# eth_part.net
KiCad netlist of a schematic drawn in Altium Designer
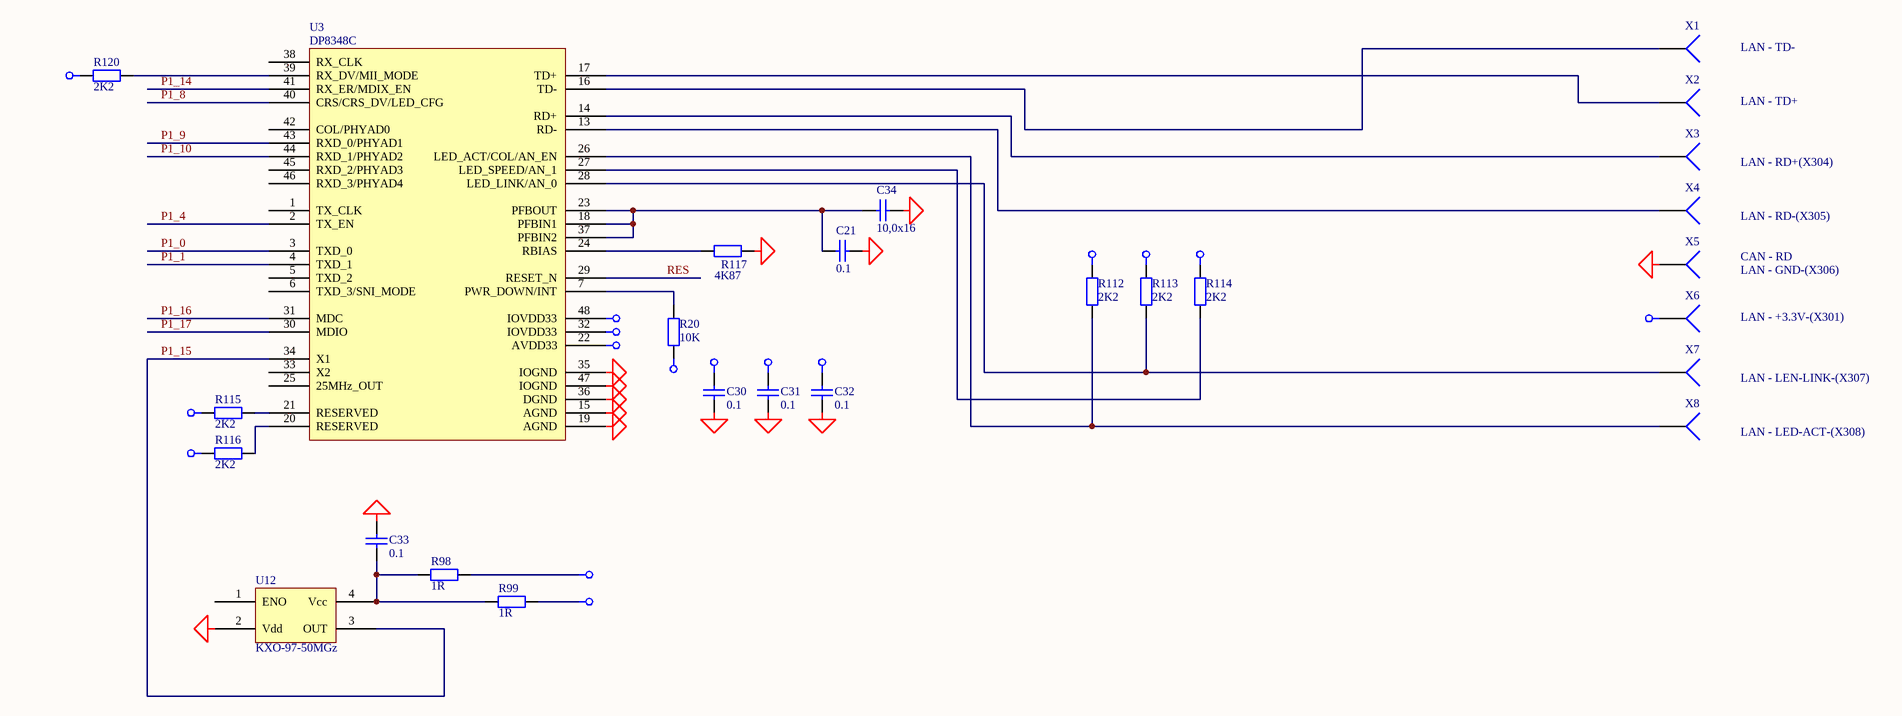
[diagram p0: eth_part.SchDoc]

(export (version "E")
  (design (tool "Eeschema 10.0.6"))
  (components
    (comp (ref "C21")
      (value "0.1")
      (footprint "C3216-1206")
      (description "Capacitor (Semiconductor SIM Model)")
      (fields (field (name "MANUFACTURER") "Generic Components") (field (name "PUBLISHER") "Altium Limited"))
      (libsource (lib "Miscellaneous Devices") (part "Cap Semi"))
    )
    (comp (ref "C30")
      (value "0.1")
      (footprint "_1206")
      (description "Capacitor (Semiconductor SIM Model)")
      (fields (field (name "MANUFACTURER") "Generic Components") (field (name "PUBLISHER") "Altium Limited"))
      (libsource (lib "Miscellaneous Devices") (part "Cap Semi"))
    )
    (comp (ref "C31")
      (value "0.1")
      (footprint "_1206")
      (description "Capacitor (Semiconductor SIM Model)")
      (fields (field (name "MANUFACTURER") "Generic Components") (field (name "PUBLISHER") "Altium Limited"))
      (libsource (lib "Miscellaneous Devices") (part "Cap Semi"))
    )
    (comp (ref "C32")
      (value "0.1")
      (footprint "_1206")
      (description "Capacitor (Semiconductor SIM Model)")
      (fields (field (name "MANUFACTURER") "Generic Components") (field (name "PUBLISHER") "Altium Limited"))
      (libsource (lib "Miscellaneous Devices") (part "Cap Semi"))
    )
    (comp (ref "C33")
      (value "0.1")
      (footprint "_1206")
      (description "Capacitor (Semiconductor SIM Model)")
      (fields (field (name "MANUFACTURER") "Generic Components") (field (name "PUBLISHER") "Altium Limited"))
      (libsource (lib "Miscellaneous Devices") (part "Cap Semi"))
    )
    (comp (ref "C34")
      (value "10,0x16")
      (footprint "C3216-1206")
      (description "Capacitor (Semiconductor SIM Model)")
      (fields (field (name "MANUFACTURER") "Generic Components") (field (name "PUBLISHER") "Altium Limited"))
      (libsource (lib "Miscellaneous Devices") (part "Cap Semi"))
    )
    (comp (ref "R20")
      (value "10K")
      (footprint "_1206")
      (description "Resistor")
      (fields (field (name "MANUFACTURER") "Generic Components") (field (name "PUBLISHER") "Altium Limited"))
      (libsource (lib "") (part "Res2_2"))
    )
    (comp (ref "R98")
      (value "1R")
      (footprint "_1206")
      (description "Resistor")
      (fields (field (name "MANUFACTURER") "Generic Components") (field (name "PUBLISHER") "Altium Limited"))
      (libsource (lib "") (part "Res2_1"))
    )
    (comp (ref "R99")
      (value "1R")
      (footprint "_1206")
      (description "Resistor")
      (fields (field (name "MANUFACTURER") "Generic Components") (field (name "PUBLISHER") "Altium Limited"))
      (libsource (lib "") (part "Res2_1"))
    )
    (comp (ref "R112")
      (value "2K2")
      (footprint "_1206")
      (description "Resistor")
      (fields (field (name "MANUFACTURER") "Generic Components") (field (name "PUBLISHER") "Altium Limited"))
      (libsource (lib "Miscellaneous Devices") (part "Res2"))
    )
    (comp (ref "R113")
      (value "2K2")
      (footprint "_1206")
      (description "Resistor")
      (fields (field (name "MANUFACTURER") "Generic Components") (field (name "PUBLISHER") "Altium Limited"))
      (libsource (lib "Miscellaneous Devices") (part "Res2"))
    )
    (comp (ref "R114")
      (value "2K2")
      (footprint "_1206")
      (description "Resistor")
      (fields (field (name "MANUFACTURER") "Generic Components") (field (name "PUBLISHER") "Altium Limited"))
      (libsource (lib "Miscellaneous Devices") (part "Res2"))
    )
    (comp (ref "R115")
      (value "2K2")
      (footprint "_1206")
      (description "Resistor")
      (fields (field (name "MANUFACTURER") "Generic Components") (field (name "PUBLISHER") "Altium Limited"))
      (libsource (lib "") (part "Res2_3"))
    )
    (comp (ref "R116")
      (value "2K2")
      (footprint "_1206")
      (description "Resistor")
      (fields (field (name "MANUFACTURER") "Generic Components") (field (name "PUBLISHER") "Altium Limited"))
      (libsource (lib "") (part "Res2_3"))
    )
    (comp (ref "R117")
      (value "4K87")
      (footprint "_1206")
      (description "Resistor")
      (fields (field (name "MANUFACTURER") "Generic Components") (field (name "PUBLISHER") "Altium Limited"))
      (libsource (lib "") (part "Res2_3"))
    )
    (comp (ref "R120")
      (value "2K2")
      (footprint "_1206")
      (description "Resistor")
      (fields (field (name "MANUFACTURER") "Generic Components") (field (name "PUBLISHER") "Altium Limited"))
      (libsource (lib "") (part "Res2_3"))
    )
    (comp (ref "U3") (value "DP8348C") (footprint "F-QFP7X7-G48/N") (libsource (lib "PAL") (part "DP8348C")))
    (comp (ref "U12") (value "KXO-97-50MGz") (footprint "KXO-97") (libsource (lib "PAL") (part "KXO-97")))
    (comp (ref "X1")
      (value "~")
      (footprint "PIN1")
      (description "Socket")
      (fields (field (name "MANUFACTURER") "Generic Components") (field (name "PUBLISHER") "Altium Limited"))
      (libsource (lib "Miscellaneous Connectors") (part "Socket"))
    )
    (comp (ref "X2")
      (value "~")
      (footprint "PIN1")
      (description "Socket")
      (fields (field (name "MANUFACTURER") "Generic Components") (field (name "PUBLISHER") "Altium Limited"))
      (libsource (lib "Miscellaneous Connectors") (part "Socket"))
    )
    (comp (ref "X3")
      (value "~")
      (footprint "PIN1")
      (description "Socket")
      (fields (field (name "MANUFACTURER") "Generic Components") (field (name "PUBLISHER") "Altium Limited"))
      (libsource (lib "Miscellaneous Connectors") (part "Socket"))
    )
    (comp (ref "X4")
      (value "~")
      (footprint "PIN1")
      (description "Socket")
      (fields (field (name "MANUFACTURER") "Generic Components") (field (name "PUBLISHER") "Altium Limited"))
      (libsource (lib "Miscellaneous Connectors") (part "Socket"))
    )
    (comp (ref "X5")
      (value "~")
      (footprint "PIN1")
      (description "Socket")
      (fields (field (name "MANUFACTURER") "Generic Components") (field (name "PUBLISHER") "Altium Limited"))
      (libsource (lib "Miscellaneous Connectors") (part "Socket"))
    )
    (comp (ref "X6")
      (value "~")
      (footprint "PIN1")
      (description "Socket")
      (fields (field (name "MANUFACTURER") "Generic Components") (field (name "PUBLISHER") "Altium Limited"))
      (libsource (lib "Miscellaneous Connectors") (part "Socket"))
    )
    (comp (ref "X7")
      (value "~")
      (footprint "PIN1")
      (description "Socket")
      (fields (field (name "MANUFACTURER") "Generic Components") (field (name "PUBLISHER") "Altium Limited"))
      (libsource (lib "Miscellaneous Connectors") (part "Socket"))
    )
    (comp (ref "X8")
      (value "~")
      (footprint "PIN1")
      (description "Socket")
      (fields (field (name "MANUFACTURER") "Generic Components") (field (name "PUBLISHER") "Altium Limited"))
      (libsource (lib "Miscellaneous Connectors") (part "Socket"))
    )
  )
  (nets
    (net (code "1") (name "+3v3") (class "Default")
      (node (ref "C30") (pin "1") (pinfunction "1_1") (pintype "passive"))
      (node (ref "C31") (pin "1") (pinfunction "1_1") (pintype "passive"))
      (node (ref "C32") (pin "1") (pinfunction "1_1") (pintype "passive"))
      (node (ref "R112") (pin "2") (pinfunction "2_2") (pintype "passive"))
      (node (ref "R113") (pin "2") (pinfunction "2_2") (pintype "passive"))
      (node (ref "R114") (pin "2") (pinfunction "2_2") (pintype "passive"))
      (node (ref "R115") (pin "2") (pinfunction "2_2") (pintype "passive"))
      (node (ref "R116") (pin "2") (pinfunction "2_2") (pintype "passive"))
      (node (ref "R120") (pin "2") (pinfunction "2_2") (pintype "passive"))
      (node (ref "R20") (pin "2") (pinfunction "2_2") (pintype "passive"))
      (node (ref "R99") (pin "2") (pinfunction "2_2") (pintype "passive"))
      (node (ref "U3") (pin "22") (pinfunction "AVDD33_22") (pintype "passive"))
      (node (ref "U3") (pin "32") (pinfunction "IOVDD33_32") (pintype "passive"))
      (node (ref "U3") (pin "48") (pinfunction "IOVDD33_48") (pintype "passive"))
      (node (ref "X6") (pin "1") (pinfunction "1_1") (pintype "passive"))
    )
    (net (code "2") (name "+5v") (class "Default")
      (node (ref "R98") (pin "2") (pinfunction "2_2") (pintype "passive"))
    )
    (net (code "3") (name "/P1_0") (class "Default")
      (node (ref "U3") (pin "3") (pinfunction "TXD_0_3") (pintype "passive"))
    )
    (net (code "4") (name "/P1_1") (class "Default")
      (node (ref "U3") (pin "4") (pinfunction "TXD_1_4") (pintype "passive"))
    )
    (net (code "5") (name "/P1_4") (class "Default")
      (node (ref "U3") (pin "2") (pinfunction "TX_EN_2") (pintype "passive"))
    )
    (net (code "6") (name "/P1_8") (class "Default")
      (node (ref "U3") (pin "40") (pinfunction "CRS/CRS_DV/LED_CFG_40") (pintype "passive"))
    )
    (net (code "7") (name "/P1_9") (class "Default")
      (node (ref "U3") (pin "43") (pinfunction "RXD_0/PHYAD1_43") (pintype "passive"))
    )
    (net (code "8") (name "/P1_10") (class "Default")
      (node (ref "U3") (pin "44") (pinfunction "RXD_1/PHYAD2_44") (pintype "passive"))
    )
    (net (code "9") (name "/P1_14") (class "Default")
      (node (ref "U3") (pin "41") (pinfunction "RX_ER/MDIX_EN_41") (pintype "passive"))
    )
    (net (code "10") (name "/P1_15") (class "Default")
      (node (ref "U12") (pin "3") (pinfunction "OUT_3") (pintype "passive"))
      (node (ref "U3") (pin "34") (pinfunction "X1_34") (pintype "passive"))
    )
    (net (code "11") (name "/P1_16") (class "Default")
      (node (ref "U3") (pin "31") (pinfunction "MDC_31") (pintype "passive"))
    )
    (net (code "12") (name "/P1_17") (class "Default")
      (node (ref "U3") (pin "30") (pinfunction "MDIO_30") (pintype "passive"))
    )
    (net (code "13") (name "/RES") (class "Default")
      (node (ref "U3") (pin "29") (pinfunction "RESET_N_29") (pintype "passive"))
    )
    (net (code "14") (name "GND") (class "Default")
      (node (ref "C21") (pin "2") (pinfunction "2_2") (pintype "passive"))
      (node (ref "C30") (pin "2") (pinfunction "2_2") (pintype "passive"))
      (node (ref "C31") (pin "2") (pinfunction "2_2") (pintype "passive"))
      (node (ref "C32") (pin "2") (pinfunction "2_2") (pintype "passive"))
      (node (ref "C33") (pin "2") (pinfunction "2_2") (pintype "passive"))
      (node (ref "C34") (pin "2") (pinfunction "2_2") (pintype "passive"))
      (node (ref "R117") (pin "1") (pinfunction "1_1") (pintype "passive"))
      (node (ref "U12") (pin "2") (pinfunction "Vdd_2") (pintype "passive"))
      (node (ref "U3") (pin "15") (pinfunction "AGND_15") (pintype "passive"))
      (node (ref "U3") (pin "19") (pinfunction "AGND_19") (pintype "passive"))
      (node (ref "U3") (pin "35") (pinfunction "IOGND_35") (pintype "passive"))
      (node (ref "U3") (pin "36") (pinfunction "DGND_36") (pintype "passive"))
      (node (ref "U3") (pin "47") (pinfunction "IOGND_47") (pintype "passive"))
      (node (ref "X5") (pin "1") (pinfunction "1_1") (pintype "passive"))
    )
    (net (code "15") (name "Net-(R115-Pad1)") (class "Default")
      (node (ref "R115") (pin "1") (pinfunction "1_1") (pintype "passive"))
      (node (ref "U3") (pin "21") (pinfunction "RESERVED_21") (pintype "passive"))
    )
    (net (code "16") (name "Net-(R116-Pad1)") (class "Default")
      (node (ref "R116") (pin "1") (pinfunction "1_1") (pintype "passive"))
      (node (ref "U3") (pin "20") (pinfunction "RESERVED_20") (pintype "passive"))
    )
    (net (code "17") (name "Net-(U3-LED_ACT{slash}COL{slash}AN_EN)") (class "Default")
      (node (ref "R112") (pin "1") (pinfunction "1_1") (pintype "passive"))
      (node (ref "U3") (pin "26") (pinfunction "LED_ACT/COL/AN_EN_26") (pintype "passive"))
      (node (ref "X8") (pin "1") (pinfunction "1_1") (pintype "passive"))
    )
    (net (code "18") (name "Net-(U3-LED_LINK{slash}AN_0)") (class "Default")
      (node (ref "R113") (pin "1") (pinfunction "1_1") (pintype "passive"))
      (node (ref "U3") (pin "28") (pinfunction "LED_LINK/AN_0_28") (pintype "passive"))
      (node (ref "X7") (pin "1") (pinfunction "1_1") (pintype "passive"))
    )
    (net (code "19") (name "Net-(U3-LED_SPEED{slash}AN_1)") (class "Default")
      (node (ref "R114") (pin "1") (pinfunction "1_1") (pintype "passive"))
      (node (ref "U3") (pin "27") (pinfunction "LED_SPEED/AN_1_27") (pintype "passive"))
    )
    (net (code "20") (name "Net-(U3-PFBIN1)") (class "Default")
      (node (ref "C21") (pin "1") (pinfunction "1_1") (pintype "passive"))
      (node (ref "C34") (pin "1") (pinfunction "1_1") (pintype "passive"))
      (node (ref "U3") (pin "18") (pinfunction "PFBIN1_18") (pintype "passive"))
      (node (ref "U3") (pin "23") (pinfunction "PFBOUT_23") (pintype "passive"))
      (node (ref "U3") (pin "37") (pinfunction "PFBIN2_37") (pintype "passive"))
    )
    (net (code "21") (name "Net-(U3-PWR_DOWN{slash}INT)") (class "Default")
      (node (ref "R20") (pin "1") (pinfunction "1_1") (pintype "passive"))
      (node (ref "U3") (pin "7") (pinfunction "PWR_DOWN/INT_7") (pintype "passive"))
    )
    (net (code "22") (name "Net-(U3-RBIAS)") (class "Default")
      (node (ref "R117") (pin "2") (pinfunction "2_2") (pintype "passive"))
      (node (ref "U3") (pin "24") (pinfunction "RBIAS_24") (pintype "passive"))
    )
    (net (code "23") (name "Net-(U3-RD+)") (class "Default")
      (node (ref "U3") (pin "14") (pinfunction "RD+_14") (pintype "passive"))
      (node (ref "X3") (pin "1") (pinfunction "1_1") (pintype "passive"))
    )
    (net (code "24") (name "Net-(U3-RD-)") (class "Default")
      (node (ref "U3") (pin "13") (pinfunction "RD-_13") (pintype "passive"))
      (node (ref "X4") (pin "1") (pinfunction "1_1") (pintype "passive"))
    )
    (net (code "25") (name "Net-(U3-RX_DV{slash}MII_MODE)") (class "Default")
      (node (ref "R120") (pin "1") (pinfunction "1_1") (pintype "passive"))
      (node (ref "U3") (pin "39") (pinfunction "RX_DV/MII_MODE_39") (pintype "passive"))
    )
    (net (code "26") (name "Net-(U3-TD+)") (class "Default")
      (node (ref "U3") (pin "17") (pinfunction "TD+_17") (pintype "passive"))
      (node (ref "X2") (pin "1") (pinfunction "1_1") (pintype "passive"))
    )
    (net (code "27") (name "Net-(U3-TD-)") (class "Default")
      (node (ref "U3") (pin "16") (pinfunction "TD-_16") (pintype "passive"))
      (node (ref "X1") (pin "1") (pinfunction "1_1") (pintype "passive"))
    )
    (net (code "28") (name "Net-(U12-Vcc)") (class "Default")
      (node (ref "C33") (pin "1") (pinfunction "1_1") (pintype "passive"))
      (node (ref "R98") (pin "1") (pinfunction "1_1") (pintype "passive"))
      (node (ref "R99") (pin "1") (pinfunction "1_1") (pintype "passive"))
      (node (ref "U12") (pin "4") (pinfunction "Vcc_4") (pintype "passive"))
    )
    (net (code "29") (name "unconnected-(U3-25MHz_OUT-Pad25)") (class "Default")
      (node (ref "U3") (pin "25") (pinfunction "25MHz_OUT_25") (pintype "passive"))
    )
    (net (code "30") (name "unconnected-(U3-COL{slash}PHYAD0-Pad42)") (class "Default")
      (node (ref "U3") (pin "42") (pinfunction "COL/PHYAD0_42") (pintype "passive"))
    )
    (net (code "31") (name "unconnected-(U3-RXD_2{slash}PHYAD3-Pad45)") (class "Default")
      (node (ref "U3") (pin "45") (pinfunction "RXD_2/PHYAD3_45") (pintype "passive"))
    )
    (net (code "32") (name "unconnected-(U3-RXD_3{slash}PHYAD4-Pad46)") (class "Default")
      (node (ref "U3") (pin "46") (pinfunction "RXD_3/PHYAD4_46") (pintype "passive"))
    )
    (net (code "33") (name "unconnected-(U3-RX_CLK-Pad38)") (class "Default")
      (node (ref "U3") (pin "38") (pinfunction "RX_CLK_38") (pintype "passive"))
    )
    (net (code "34") (name "unconnected-(U3-TXD_2-Pad5)") (class "Default")
      (node (ref "U3") (pin "5") (pinfunction "TXD_2_5") (pintype "passive"))
    )
    (net (code "35") (name "unconnected-(U3-TXD_3{slash}SNI_MODE-Pad6)") (class "Default")
      (node (ref "U3") (pin "6") (pinfunction "TXD_3/SNI_MODE_6") (pintype "passive"))
    )
    (net (code "36") (name "unconnected-(U3-TX_CLK-Pad1)") (class "Default")
      (node (ref "U3") (pin "1") (pinfunction "TX_CLK_1") (pintype "passive"))
    )
    (net (code "37") (name "unconnected-(U3-X2-Pad33)") (class "Default")
      (node (ref "U3") (pin "33") (pinfunction "X2_33") (pintype "passive"))
    )
    (net (code "38") (name "unconnected-(U12-ENO-Pad1)") (class "Default")
      (node (ref "U12") (pin "1") (pinfunction "ENO_1") (pintype "passive"))
    )
  )
)
